# ShutdownSegement.net
KiCad netlist of a schematic drawn in Altium Designer
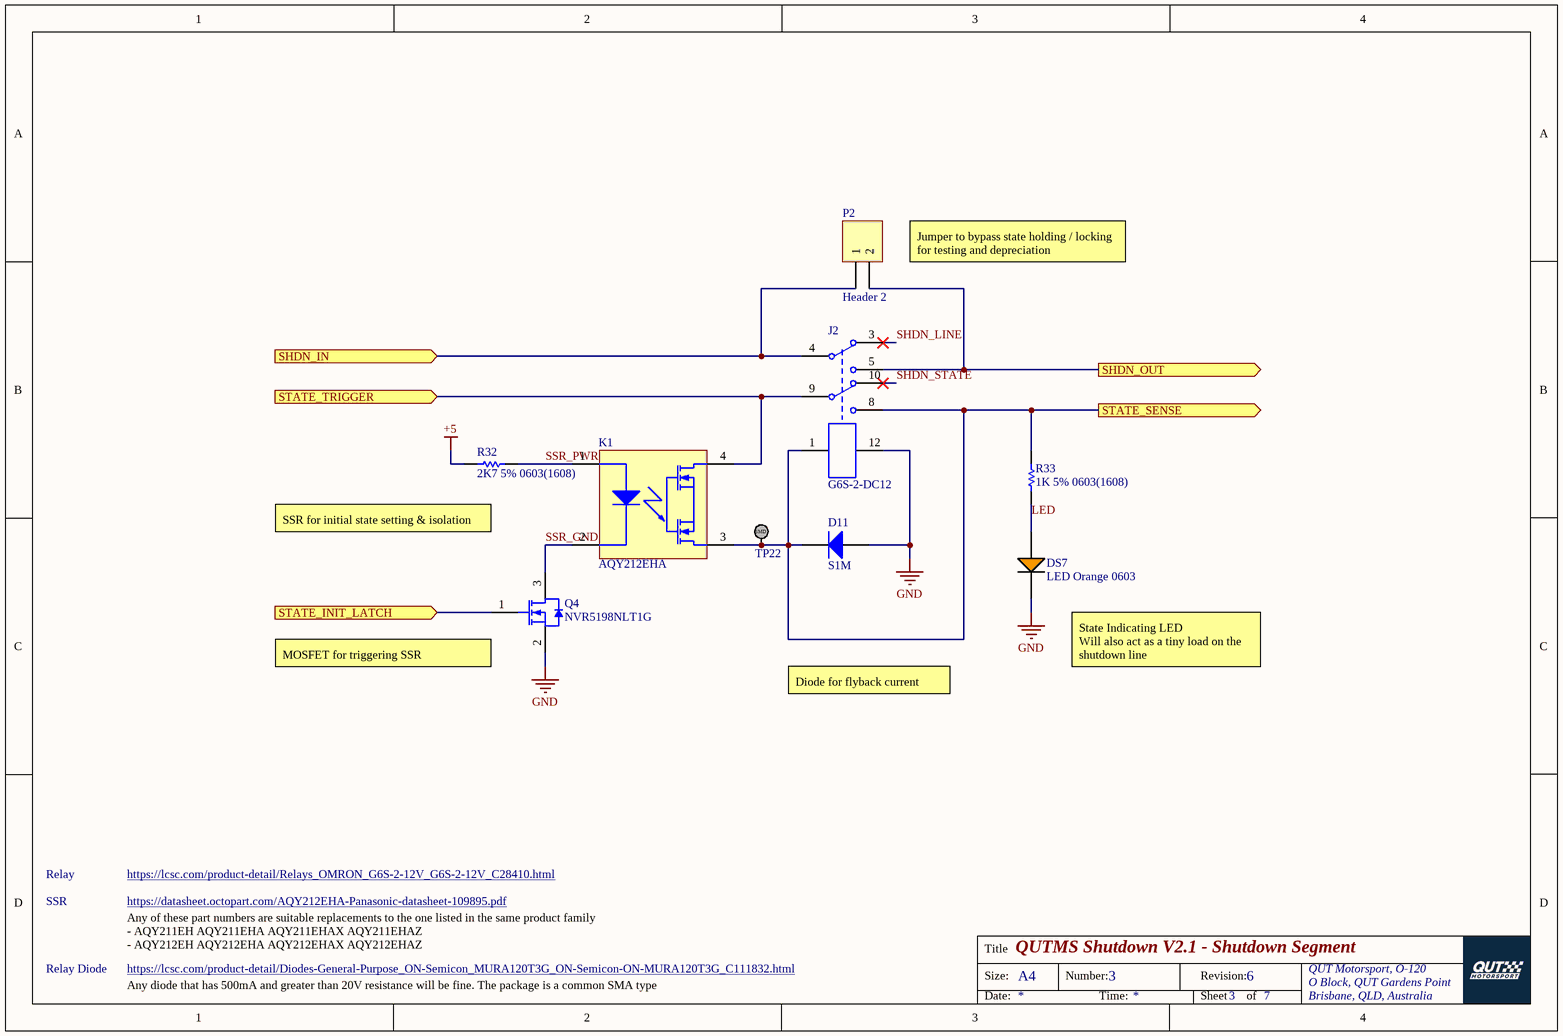
[diagram p0: ShutdownSegement.SchDoc]

(export (version "E")
  (design (tool "Eeschema 10.0.6"))
  (components
    (comp (ref "D11")
      (value "S1M")
      (footprint "FAIR-DO-214AC-2_V")
      (description "General Purpose Rectifier, 1 A, 1000 V, -55 to 150 degC, 2-Pin DO-214AC, RoHS, Tape and Reel")
      (fields (field (name "MANUFACTURER") "Fairchild"))
      (libsource (lib "Altium Content Vault") (part "D-AK-2"))
    )
    (comp (ref "DS7")
      (value "LED Orange 0603")
      (footprint "LED ORANGE 0603")
      (libsource (lib "QUTMS_LEDLibrary") (part "LED ORANGE 0603"))
    )
    (comp (ref "J2")
      (value "G6S-2-DC12")
      (footprint "G6S-2")
      (description "Telecom Non Latching 12VDC DPDT 2A Through Hole Relays RoHS")
      (libsource (lib "QUTMS_RelayLibrary") (part "G6S-2-DC12"))
    )
    (comp (ref "K1")
      (value "AQY212EHA")
      (footprint "PNSC-DIP4(SMT)_V")
      (fields (field (name "MANUFACTURER") "Panasonic"))
      (libsource (lib "Altium Content Vault") (part "PNSC-AQY212EH-DIP4"))
    )
    (comp (ref "P2")
      (value "Header 2")
      (footprint "HDR1X2")
      (description "Header, 2-Pin")
      (fields (field (name "PUBLISHER") "Altium Limited"))
      (libsource (lib "Miscellaneous Connectors") (part "Header 2"))
    )
    (comp (ref "Q4")
      (value "NVR5198NLT1G")
      (footprint "ONSC-SOT-23-3-318-08_V")
      (description "Power MOSFET, 60 V, 155 mOhm, Single N-Channel Logic Level, 3-Pin SOT-23, Pb-Free, Tape and Reel")
      (fields (field (name "MANUFACTURER") "On Semiconductor"))
      (libsource (lib "Altium Content Vault") (part "ONSC-NMOS-G1S2D3-3"))
    )
    (comp (ref "R32")
      (value "2K7 5% 0603(1608)")
      (footprint "RESC0603(1608)_M")
      (description "2K7 0.1W 5% 0603 (1608 Metric)  SMD")
      (fields (field (name "TOLERANCE") "5 %") (field (name "POWER") "0.1 W"))
      (libsource (lib "Altium Content Vault") (part "RES"))
    )
    (comp (ref "R33")
      (value "1K 5% 0603(1608)")
      (footprint "RESC0603(1608)_L")
      (description "1K 0.1W 5% 0603 (1608 Metric)  SMD")
      (fields (field (name "TOLERANCE") "5 %") (field (name "POWER") "0.1 W"))
      (libsource (lib "Altium Content Vault") (part "RES"))
    )
    (comp (ref "TP22")
      (value "TestPoint_SMD")
      (footprint "TestPointSMD")
      (libsource (lib "StandardTest") (part "TestPoint_SMD"))
    )
  )
  (nets
    (net (code "1") (name "+5") (class "Default")
      (node (ref "R32") (pin "1") (pinfunction "1_1") (pintype "passive"))
    )
    (net (code "2") (name "/LED") (class "Default")
      (node (ref "DS7") (pin "1") (pinfunction "A_1") (pintype "passive"))
      (node (ref "R33") (pin "1") (pinfunction "1_1") (pintype "passive"))
    )
    (net (code "3") (name "/SHDN_IN") (class "Default")
      (node (ref "J2") (pin "4") (pinfunction "4_4") (pintype "passive"))
      (node (ref "P2") (pin "1") (pinfunction "1_1") (pintype "passive"))
    )
    (net (code "4") (name "/SHDN_LINE") (class "Default")
      (node (ref "J2") (pin "3") (pinfunction "3_3") (pintype "passive+no_connect"))
    )
    (net (code "5") (name "/SHDN_OUT") (class "Default")
      (node (ref "J2") (pin "5") (pinfunction "5_5") (pintype "passive"))
      (node (ref "P2") (pin "2") (pinfunction "2_2") (pintype "passive"))
    )
    (net (code "6") (name "/SHDN_STATE") (class "Default")
      (node (ref "J2") (pin "10") (pinfunction "10_10") (pintype "passive+no_connect"))
    )
    (net (code "7") (name "/SSR_GND") (class "Default")
      (node (ref "K1") (pin "2") (pinfunction "2_2") (pintype "passive"))
      (node (ref "Q4") (pin "3") (pinfunction "D_3") (pintype "passive"))
    )
    (net (code "8") (name "/SSR_PWR") (class "Default")
      (node (ref "K1") (pin "1") (pinfunction "1_1") (pintype "passive"))
      (node (ref "R32") (pin "2") (pinfunction "2_2") (pintype "passive"))
    )
    (net (code "9") (name "/STATE_INIT_LATCH") (class "Default")
      (node (ref "Q4") (pin "1") (pinfunction "G_1") (pintype "passive"))
    )
    (net (code "10") (name "/STATE_SENSE") (class "Default")
      (node (ref "D11") (pin "2") (pinfunction "K_2") (pintype "passive"))
      (node (ref "J2") (pin "1") (pinfunction "1_1") (pintype "passive"))
      (node (ref "J2") (pin "8") (pinfunction "8_8") (pintype "passive"))
      (node (ref "K1") (pin "3") (pinfunction "3_3") (pintype "passive"))
      (node (ref "R33") (pin "2") (pinfunction "2_2") (pintype "passive"))
      (node (ref "TP22") (pin "1") (pinfunction "1_1") (pintype "passive"))
    )
    (net (code "11") (name "/STATE_TRIGGER") (class "Default")
      (node (ref "J2") (pin "9") (pinfunction "9_9") (pintype "passive"))
      (node (ref "K1") (pin "4") (pinfunction "4_4") (pintype "passive"))
    )
    (net (code "12") (name "GND") (class "Default")
      (node (ref "D11") (pin "1") (pinfunction "A_1") (pintype "passive"))
      (node (ref "DS7") (pin "2") (pinfunction "C_2") (pintype "passive"))
      (node (ref "J2") (pin "12") (pinfunction "12_12") (pintype "passive"))
      (node (ref "Q4") (pin "2") (pinfunction "S_2") (pintype "passive"))
    )
  )
)
